# CNEPuckCPURevF.net
KiCad netlist of a schematic drawn in Altium Designer
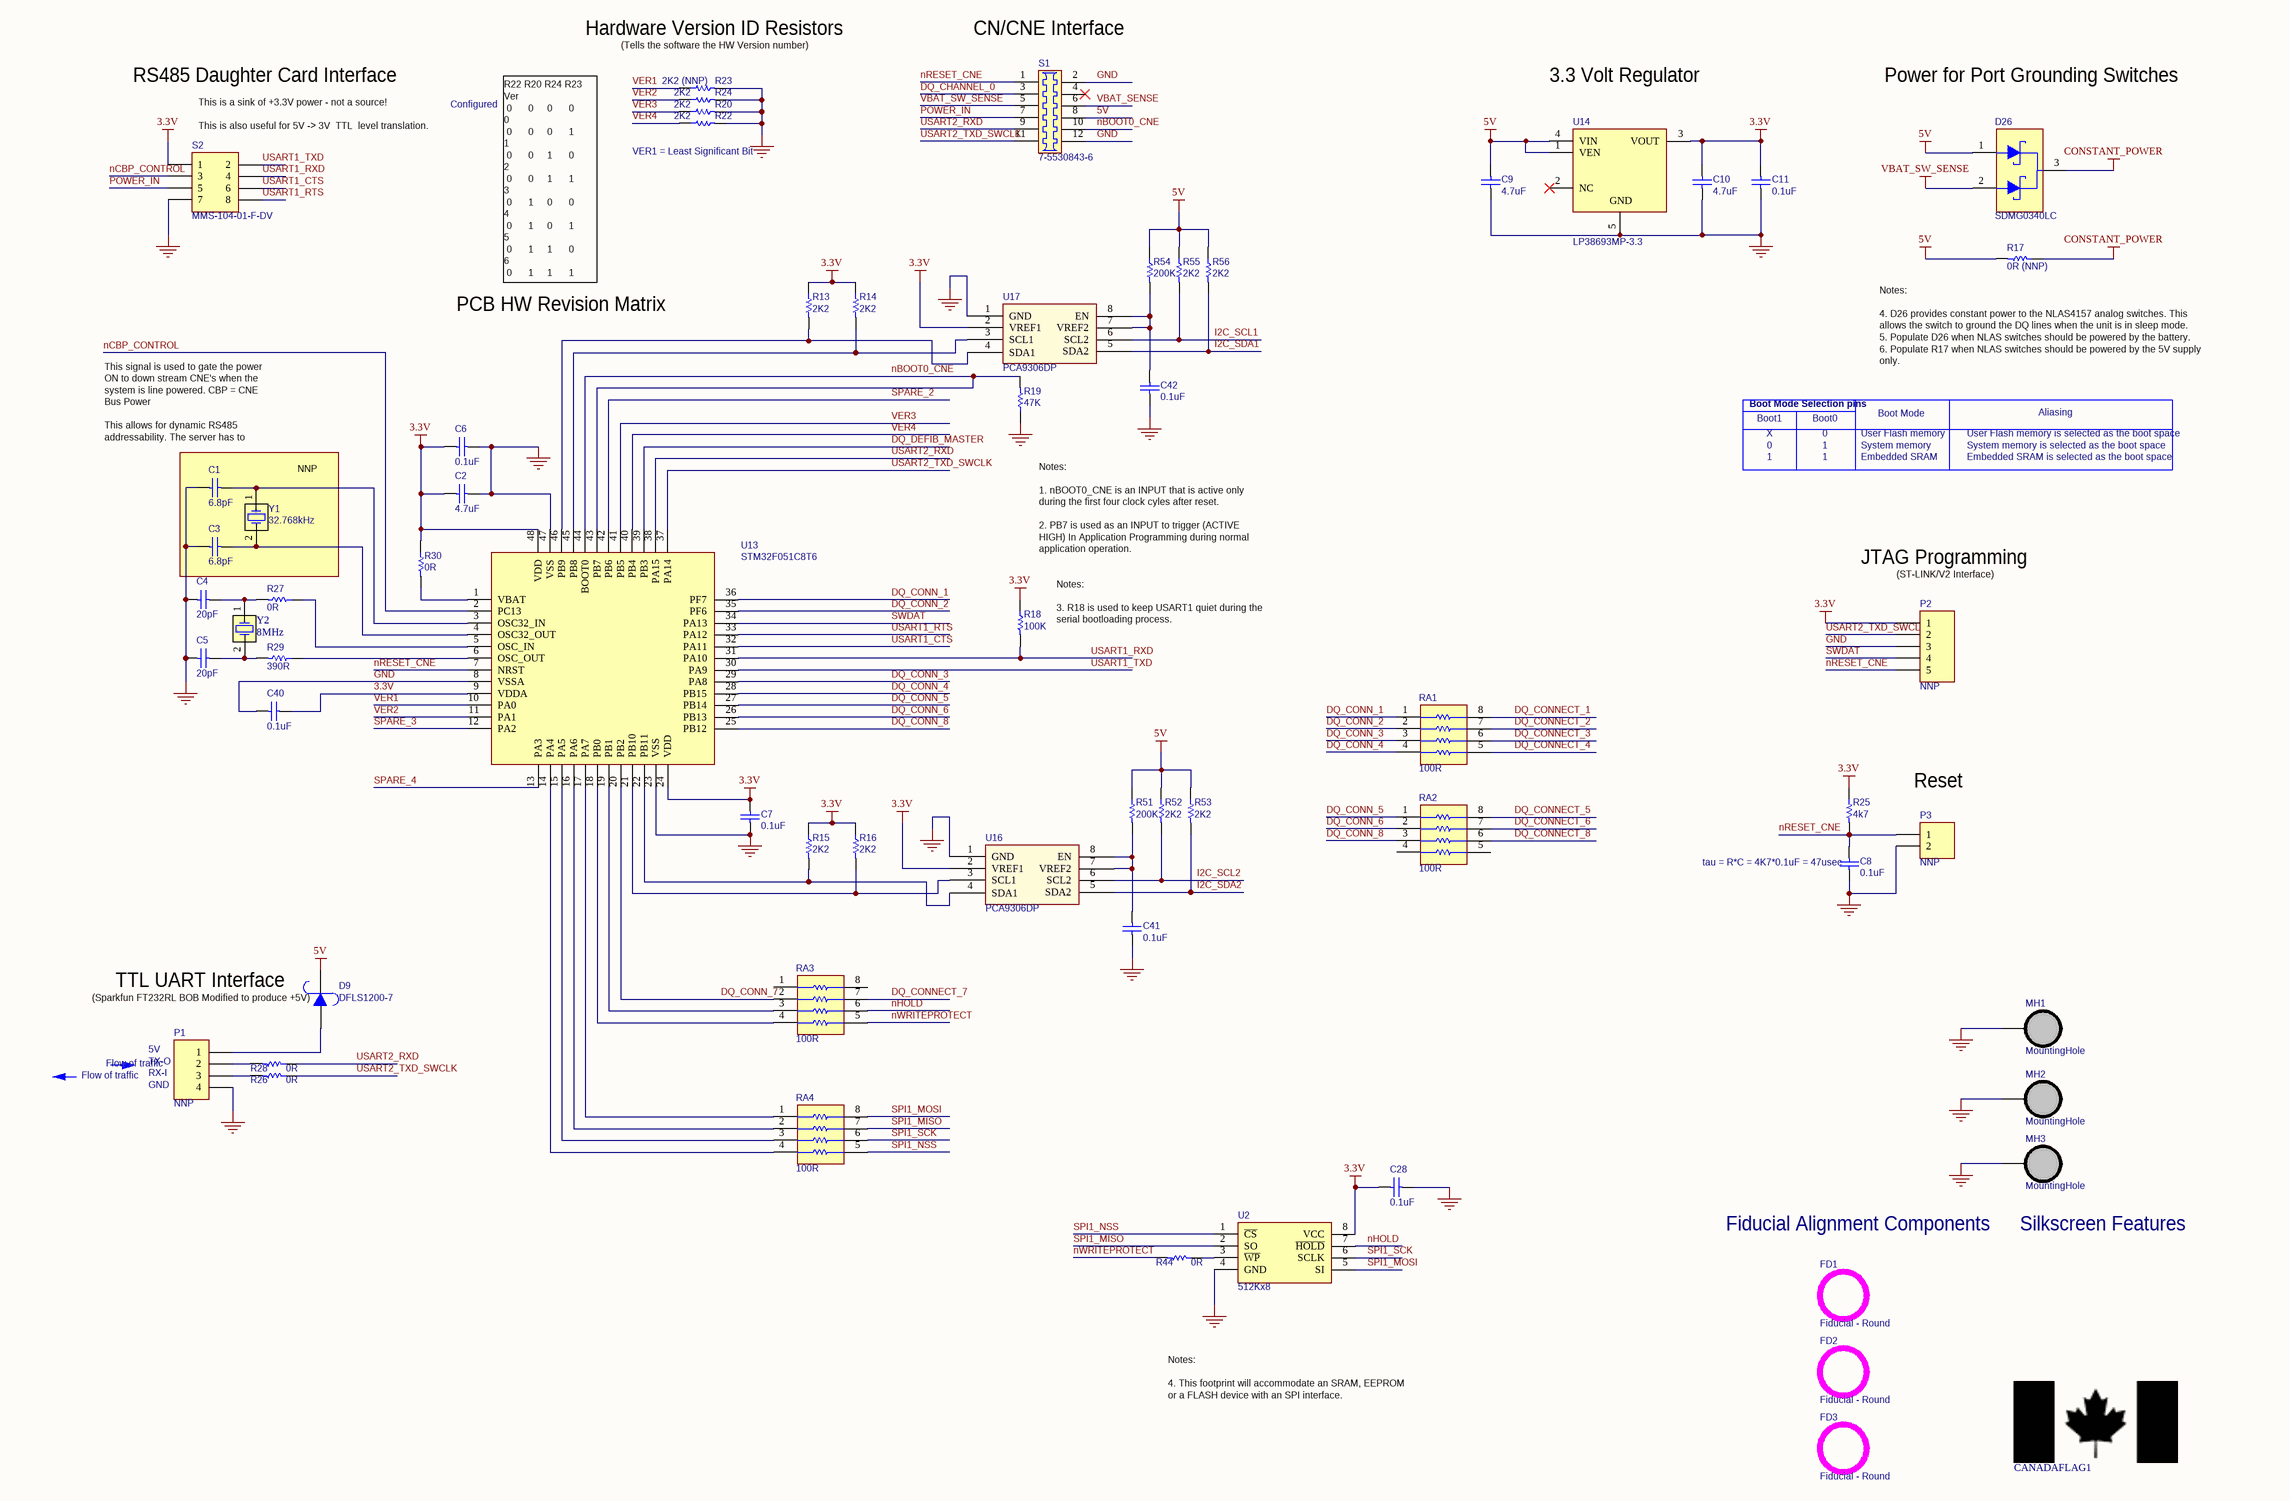
[diagram p0: CNEPuckCPURevF.SchDoc]

(export (version "E")
  (design (tool "Eeschema 10.0.6"))
  (components
    (comp (ref "C1")
      (value "6.8pF")
      (footprint "RC0603")
      (description "CAP CER 6.8PF 50V NP0 0603")
      (fields
        (field (name "MANUFACTURER") "TDK Corporation")
        (field (name "MANUFACTURER PART NUMBER") "C1608C0G1H6R8D")
      )
      (libsource (lib "Swage") (part "C1608C0G1H6R8D"))
    )
    (comp (ref "C2")
      (value "4.7uF")
      (footprint "RC0603")
      (description "CAP CER 4.7UF 10V 10% X5R 0603")
      (fields
        (field (name "MANUFACTURER") "TDK Corporation")
        (field (name "MANUFACTURER PART NUMBER") "C1608X5R1A475K/0.50")
      )
      (libsource (lib "Swage") (part "C1608X5R1A475K/0.50"))
    )
    (comp (ref "C3")
      (value "6.8pF")
      (footprint "RC0603")
      (description "CAP CER 6.8PF 50V NP0 0603")
      (fields
        (field (name "MANUFACTURER") "TDK Corporation")
        (field (name "MANUFACTURER PART NUMBER") "C1608C0G1H6R8D")
      )
      (libsource (lib "Swage") (part "C1608C0G1H6R8D"))
    )
    (comp (ref "C4")
      (value "20pF")
      (footprint "RC0603")
      (description "CAP CER 20PF 50V 5% NPO 0603")
      (fields
        (field (name "MANUFACTURER") "Yageo")
        (field (name "MANUFACTURER PART NUMBER") "CC0603JRNPO9BN200")
      )
      (libsource (lib "Swage") (part "CC0603JRNPO9BN200"))
    )
    (comp (ref "C5")
      (value "20pF")
      (footprint "RC0603")
      (description "CAP CER 20PF 50V 5% NPO 0603")
      (fields
        (field (name "MANUFACTURER") "Yageo")
        (field (name "MANUFACTURER PART NUMBER") "CC0603JRNPO9BN200")
      )
      (libsource (lib "Swage") (part "CC0603JRNPO9BN200"))
    )
    (comp (ref "C6")
      (value "0.1uF")
      (footprint "RC0603")
      (description "CAP CERM .1UF 10% 16V X7R 0603")
      (fields (field (name "TOLERANCE") "±10%") (field (name "MANUFACTURER PART NUMBER") "0603YC104KAT2A"))
      (libsource (lib "Swage") (part "0603YC104KAT2A"))
    )
    (comp (ref "C7")
      (value "0.1uF")
      (footprint "RC0603")
      (description "CAP CERM .1UF 10% 16V X7R 0603")
      (fields (field (name "TOLERANCE") "±10%") (field (name "MANUFACTURER PART NUMBER") "0603YC104KAT2A"))
      (libsource (lib "Swage") (part "0603YC104KAT2A"))
    )
    (comp (ref "C8")
      (value "0.1uF")
      (footprint "RC0603")
      (description "CAP CERM .1UF 10% 16V X7R 0603")
      (fields (field (name "TOLERANCE") "±10%") (field (name "MANUFACTURER PART NUMBER") "0603YC104KAT2A"))
      (libsource (lib "Swage") (part "0603YC104KAT2A"))
    )
    (comp (ref "C9")
      (value "4.7uF")
      (footprint "RC0603")
      (description "CAP CER 4.7UF 10V 10% X5R 0603")
      (fields
        (field (name "MANUFACTURER") "TDK Corporation")
        (field (name "MANUFACTURER PART NUMBER") "C1608X5R1A475K/0.50")
      )
      (libsource (lib "Swage") (part "C1608X5R1A475K/0.50"))
    )
    (comp (ref "C10")
      (value "4.7uF")
      (footprint "RC0603")
      (description "CAP CER 4.7UF 10V 10% X5R 0603")
      (fields
        (field (name "MANUFACTURER") "TDK Corporation")
        (field (name "MANUFACTURER PART NUMBER") "C1608X5R1A475K/0.50")
      )
      (libsource (lib "Swage") (part "C1608X5R1A475K/0.50"))
    )
    (comp (ref "C11")
      (value "0.1uF")
      (footprint "RC0603")
      (description "CAP CERM .1UF 10% 16V X7R 0603")
      (fields (field (name "TOLERANCE") "±10%") (field (name "MANUFACTURER PART NUMBER") "0603YC104KAT2A"))
      (libsource (lib "Swage") (part "0603YC104KAT2A"))
    )
    (comp (ref "C28")
      (value "0.1uF")
      (footprint "RC0603")
      (description "CAP CERM .1UF 10% 16V X7R 0603")
      (fields (field (name "TOLERANCE") "±10%") (field (name "MANUFACTURER PART NUMBER") "0603YC104KAT2A"))
      (libsource (lib "Swage") (part "0603YC104KAT2A"))
    )
    (comp (ref "C40")
      (value "0.1uF")
      (footprint "RC0603")
      (description "CAP CERM .1UF 10% 16V X7R 0603")
      (fields (field (name "TOLERANCE") "±10%") (field (name "MANUFACTURER PART NUMBER") "0603YC104KAT2A"))
      (libsource (lib "Swage") (part "0603YC104KAT2A"))
    )
    (comp (ref "C41")
      (value "0.1uF")
      (footprint "RC0603")
      (description "CAP CERM .1UF 10% 16V X7R 0603")
      (fields (field (name "TOLERANCE") "±10%") (field (name "MANUFACTURER PART NUMBER") "0603YC104KAT2A"))
      (libsource (lib "Swage") (part "0603YC104KAT2A"))
    )
    (comp (ref "C42")
      (value "0.1uF")
      (footprint "RC0603")
      (description "CAP CERM .1UF 10% 16V X7R 0603")
      (fields (field (name "TOLERANCE") "±10%") (field (name "MANUFACTURER PART NUMBER") "0603YC104KAT2A"))
      (libsource (lib "Swage") (part "0603YC104KAT2A"))
    )
    (comp (ref "CANADAFLAG1")
      (value "Canada Flag")
      (footprint "CanadaFlag500x250")
      (libsource (lib "Swage") (part "CanadaFlag"))
    )
    (comp (ref "D9")
      (value "DFLS1200-7")
      (footprint "POWERDI-123")
      (description "DIODE SCHOTTKY 1A 200V PWRDI 123")
      (fields (field (name "MANUFACTURER") "Diodes Inc"))
      (libsource (lib "Swage") (part "DFLS1200-7"))
    )
    (comp (ref "D26")
      (value "SDMG0340LC")
      (footprint "SOT-323")
      (description "DIODE SCHOTTKY 40V 30MA SOT323")
      (fields
        (field (name "MANUFACTURER") "Diodes Inc")
        (field (name "MANUFACTURER PART NUMBER") "SDMG0340LC-7-F")
      )
      (libsource (lib "Swage") (part "SDMG0340LC-7-F"))
    )
    (comp (ref "FD1")
      (value "Fiducial - Round")
      (footprint "FIDUCIAL ROUND SMALL")
      (description "Fiducial Round")
      (libsource (lib "StormaxV13") (part "Fiducial"))
    )
    (comp (ref "FD2")
      (value "Fiducial - Round")
      (footprint "FIDUCIAL ROUND SMALL")
      (description "Fiducial Round")
      (libsource (lib "StormaxV13") (part "Fiducial"))
    )
    (comp (ref "FD3")
      (value "Fiducial - Round")
      (footprint "FIDUCIAL ROUND SMALL")
      (description "Fiducial Round")
      (libsource (lib "StormaxV13") (part "Fiducial"))
    )
    (comp (ref "MH1")
      (value "MountingHole")
      (footprint "MountingHole")
      (description "PCB Mounting Hole, 0.150\" hole, 0.270\" Keepout")
      (libsource (lib "Swage") (part "MountingHole"))
    )
    (comp (ref "MH2")
      (value "MountingHole")
      (footprint "MountingHole")
      (description "PCB Mounting Hole, 0.150\" hole, 0.270\" Keepout")
      (libsource (lib "Swage") (part "MountingHole"))
    )
    (comp (ref "MH3")
      (value "MountingHole")
      (footprint "MountingHole")
      (description "PCB Mounting Hole, 0.150\" hole, 0.270\" Keepout")
      (libsource (lib "Swage") (part "MountingHole"))
    )
    (comp (ref "P1")
      (value "NNP")
      (footprint "HDR1X4")
      (description "Header, 4-Pin")
      (fields
        (field (name "MANUFACTURER") "3M")
        (field (name "MANUFACTURER PART NUMBER") "2340-6111TG")
        (field (name "PUBLISHER") "Altium Limited")
      )
      (libsource (lib "Swage") (part "Header 4"))
    )
    (comp (ref "P2")
      (value "NNP")
      (footprint "HDR1X5")
      (description "Header, 5-Pin")
      (fields
        (field (name "MANUFACTURER PART NUMBER") "2340-6111TG")
        (field (name "MANUFACTURER") "3M")
        (field (name "PUBLISHER") "Altium Limited")
      )
      (libsource (lib "Miscellaneous Connectors") (part "Header 5"))
    )
    (comp (ref "P3")
      (value "NNP")
      (footprint "HDR1X2")
      (description "Header, 2-Pin")
      (fields
        (field (name "MANUFACTURER") "3M")
        (field (name "MANUFACTURER PART NUMBER") "2340-6111TG")
        (field (name "PUBLISHER") "Altium Limited")
      )
      (libsource (lib "Miscellaneous Connectors") (part "Header 2"))
    )
    (comp (ref "R13")
      (value "2K2")
      (footprint "RC0603")
      (description "RES 2.2K OHM 1/10W 5% 0603 SMD")
      (fields
        (field (name "MANUFACTURER") "Panasonic Electronic Components")
        (field (name "MANUFACTURER PART NUMBER") "ERJ-3GEYJ222V")
      )
      (libsource (lib "Swage") (part "ERJ-3GEYJ222V"))
    )
    (comp (ref "R14")
      (value "2K2")
      (footprint "RC0603")
      (description "RES 2.2K OHM 1/10W 5% 0603 SMD")
      (fields
        (field (name "MANUFACTURER") "Panasonic Electronic Components")
        (field (name "MANUFACTURER PART NUMBER") "ERJ-3GEYJ222V")
      )
      (libsource (lib "Swage") (part "ERJ-3GEYJ222V"))
    )
    (comp (ref "R15")
      (value "2K2")
      (footprint "RC0603")
      (description "RES 2.2K OHM 1/10W 5% 0603 SMD")
      (fields
        (field (name "MANUFACTURER") "Panasonic Electronic Components")
        (field (name "MANUFACTURER PART NUMBER") "ERJ-3GEYJ222V")
      )
      (libsource (lib "Swage") (part "ERJ-3GEYJ222V"))
    )
    (comp (ref "R16")
      (value "2K2")
      (footprint "RC0603")
      (description "RES 2.2K OHM 1/10W 5% 0603 SMD")
      (fields
        (field (name "MANUFACTURER") "Panasonic Electronic Components")
        (field (name "MANUFACTURER PART NUMBER") "ERJ-3GEYJ222V")
      )
      (libsource (lib "Swage") (part "ERJ-3GEYJ222V"))
    )
    (comp (ref "R17")
      (value "0R (NNP)")
      (footprint "RC0603")
      (description "RES 0.0 OHM 1/10W 0603 SMD")
      (fields (field (name "TOLERANCE") "Jumper") (field (name "MANUFACTURER") "Panasonic - ECG"))
      (libsource (lib "Swage") (part "ERJ-3GEY0R00V"))
    )
    (comp (ref "R18")
      (value "100K")
      (footprint "RC0603")
      (description "RES 100K OHM 1/10W 5% 0603 SMD")
      (fields
        (field (name "MANUFACTURER") "Panasonic Electronic Components")
        (field (name "MANUFACTURER PART NUMBER") "ERJ-3GEYJ104V")
      )
      (libsource (lib "Swage") (part "ERJ-3GEYJ104V"))
    )
    (comp (ref "R19")
      (value "47K")
      (footprint "RC0603")
      (description "RES 47K OHM 1/10W 5% 0603 SMD")
      (fields (field (name "TOLERANCE") "±5%") (field (name "MANUFACTURER") "Panasonic - ECG"))
      (libsource (lib "Swage") (part "ERJ-3GEYJ473V"))
    )
    (comp (ref "R20")
      (value "2K2")
      (footprint "RC0603")
      (description "RES 2.2K OHM 1/10W 5% 0603 SMD")
      (fields
        (field (name "MANUFACTURER") "Panasonic Electronic Components")
        (field (name "MANUFACTURER PART NUMBER") "ERJ-3GEYJ222V")
      )
      (libsource (lib "Swage") (part "ERJ-3GEYJ222V"))
    )
    (comp (ref "R22")
      (value "2K2")
      (footprint "RC0603")
      (description "RES 2.2K OHM 1/10W 5% 0603 SMD")
      (fields
        (field (name "MANUFACTURER") "Panasonic Electronic Components")
        (field (name "MANUFACTURER PART NUMBER") "ERJ-3GEYJ222V")
      )
      (libsource (lib "Swage") (part "ERJ-3GEYJ222V"))
    )
    (comp (ref "R23")
      (value "2K2 (NNP)")
      (footprint "RC0603")
      (description "RES 2.2K OHM 1/10W 5% 0603 SMD")
      (fields
        (field (name "MANUFACTURER") "Panasonic Electronic Components")
        (field (name "MANUFACTURER PART NUMBER") "ERJ-3GEYJ222V")
      )
      (libsource (lib "Swage") (part "ERJ-3GEYJ222V"))
    )
    (comp (ref "R24")
      (value "2K2")
      (footprint "RC0603")
      (description "RES 2.2K OHM 1/10W 5% 0603 SMD")
      (fields
        (field (name "MANUFACTURER") "Panasonic Electronic Components")
        (field (name "MANUFACTURER PART NUMBER") "ERJ-3GEYJ222V")
      )
      (libsource (lib "Swage") (part "ERJ-3GEYJ222V"))
    )
    (comp (ref "R25")
      (value "4k7")
      (footprint "RC0603")
      (description "RES 4.7K OHM 1/10W 5% 0603 SMD")
      (fields
        (field (name "MANUFACTURER") "Panasonic - ECG")
        (field (name "MANUFACTURER PART NUMBER") "ERJ-3GEYJ472V")
      )
      (libsource (lib "Swage") (part "ERJ-3GEYJ472V"))
    )
    (comp (ref "R26")
      (value "0R")
      (footprint "RC0603")
      (description "RES 0.0 OHM 1/10W 0603 SMD")
      (fields (field (name "TOLERANCE") "Jumper") (field (name "MANUFACTURER") "Panasonic - ECG"))
      (libsource (lib "Swage") (part "ERJ-3GEY0R00V"))
    )
    (comp (ref "R27")
      (value "0R")
      (footprint "RC0603")
      (description "RES 0.0 OHM 1/10W 0603 SMD")
      (fields (field (name "TOLERANCE") "Jumper") (field (name "MANUFACTURER") "Panasonic - ECG"))
      (libsource (lib "Swage") (part "ERJ-3GEY0R00V"))
    )
    (comp (ref "R28")
      (value "0R")
      (footprint "RC0603")
      (description "RES 0.0 OHM 1/10W 0603 SMD")
      (fields (field (name "TOLERANCE") "Jumper") (field (name "MANUFACTURER") "Panasonic - ECG"))
      (libsource (lib "Swage") (part "ERJ-3GEY0R00V"))
    )
    (comp (ref "R29")
      (value "390R")
      (footprint "RC0603")
      (description "RES 390 OHM 1/10W 5% 0603 SMD")
      (fields
        (field (name "MANUFACTURER") "Panasonic Electronic Components")
        (field (name "MANUFACTURER PART NUMBER") "ERJ-3GEYJ391V")
      )
      (libsource (lib "Swage") (part "ERJ-3GEYJ391V"))
    )
    (comp (ref "R30")
      (value "0R")
      (footprint "RC0603")
      (description "RES 0.0 OHM 1/10W 0603 SMD")
      (fields (field (name "TOLERANCE") "Jumper") (field (name "MANUFACTURER") "Panasonic - ECG"))
      (libsource (lib "Swage") (part "ERJ-3GEY0R00V"))
    )
    (comp (ref "R44")
      (value "0R")
      (footprint "RC0603")
      (description "RES 0.0 OHM 1/10W 0603 SMD")
      (fields (field (name "TOLERANCE") "Jumper") (field (name "MANUFACTURER") "Panasonic - ECG"))
      (libsource (lib "Swage") (part "ERJ-3GEY0R00V"))
    )
    (comp (ref "R51")
      (value "200K")
      (footprint "RC0603")
      (description "RES 200K OHM 1/10W 5% 0603 SMD")
      (fields
        (field (name "MANUFACTURER") "Panasonic Electronic Components")
        (field (name "MANUFACTURER PART NUMBER") "ERJ-3GEYJ204V")
      )
      (libsource (lib "Swage") (part "ERJ-3GEYJ204V"))
    )
    (comp (ref "R52")
      (value "2K2")
      (footprint "RC0603")
      (description "RES 2.2K OHM 1/10W 5% 0603 SMD")
      (fields
        (field (name "MANUFACTURER") "Panasonic Electronic Components")
        (field (name "MANUFACTURER PART NUMBER") "ERJ-3GEYJ222V")
      )
      (libsource (lib "Swage") (part "ERJ-3GEYJ222V"))
    )
    (comp (ref "R53")
      (value "2K2")
      (footprint "RC0603")
      (description "RES 2.2K OHM 1/10W 5% 0603 SMD")
      (fields
        (field (name "MANUFACTURER") "Panasonic Electronic Components")
        (field (name "MANUFACTURER PART NUMBER") "ERJ-3GEYJ222V")
      )
      (libsource (lib "Swage") (part "ERJ-3GEYJ222V"))
    )
    (comp (ref "R54")
      (value "200K")
      (footprint "RC0603")
      (description "RES 200K OHM 1/10W 5% 0603 SMD")
      (fields
        (field (name "MANUFACTURER") "Panasonic Electronic Components")
        (field (name "MANUFACTURER PART NUMBER") "ERJ-3GEYJ204V")
      )
      (libsource (lib "Swage") (part "ERJ-3GEYJ204V"))
    )
    (comp (ref "R55")
      (value "2K2")
      (footprint "RC0603")
      (description "RES 2.2K OHM 1/10W 5% 0603 SMD")
      (fields
        (field (name "MANUFACTURER") "Panasonic Electronic Components")
        (field (name "MANUFACTURER PART NUMBER") "ERJ-3GEYJ222V")
      )
      (libsource (lib "Swage") (part "ERJ-3GEYJ222V"))
    )
    (comp (ref "R56")
      (value "2K2")
      (footprint "RC0603")
      (description "RES 2.2K OHM 1/10W 5% 0603 SMD")
      (fields
        (field (name "MANUFACTURER") "Panasonic Electronic Components")
        (field (name "MANUFACTURER PART NUMBER") "ERJ-3GEYJ222V")
      )
      (libsource (lib "Swage") (part "ERJ-3GEYJ222V"))
    )
    (comp (ref "RA1")
      (value "100R")
      (footprint "exb28v")
      (description "RES ARRAY 100 OHM 4 RES 0804")
      (fields
        (field (name "MANUFACTURER") "Panasonic Electronic Components")
        (field (name "MANUFACTURER PART NUMBER") "EXB-28V101JX")
      )
      (libsource (lib "Swage") (part "EXB-28V101JX"))
    )
    (comp (ref "RA2")
      (value "100R")
      (footprint "exb28v")
      (description "RES ARRAY 100 OHM 4 RES 0804")
      (fields
        (field (name "MANUFACTURER") "Panasonic Electronic Components")
        (field (name "MANUFACTURER PART NUMBER") "EXB-28V101JX")
      )
      (libsource (lib "Swage") (part "EXB-28V101JX"))
    )
    (comp (ref "RA3")
      (value "100R")
      (footprint "exb28v")
      (description "RES ARRAY 100 OHM 4 RES 0804")
      (fields
        (field (name "MANUFACTURER") "Panasonic Electronic Components")
        (field (name "MANUFACTURER PART NUMBER") "EXB-28V101JX")
      )
      (libsource (lib "Swage") (part "EXB-28V101JX"))
    )
    (comp (ref "RA4")
      (value "100R")
      (footprint "exb28v")
      (description "RES ARRAY 100 OHM 4 RES 0804")
      (fields
        (field (name "MANUFACTURER") "Panasonic Electronic Components")
        (field (name "MANUFACTURER PART NUMBER") "EXB-28V101JX")
      )
      (libsource (lib "Swage") (part "EXB-28V101JX"))
    )
    (comp (ref "S1")
      (value "7-5530843-6")
      (footprint "EdgeConnector-6-12")
      (description "CONN EDGECARD 6POS .100 VERT")
      (fields (field (name "MANUFACTURER") "TE Connectivity"))
      (libsource (lib "Swage") (part "7-5530843-6"))
    )
    (comp (ref "S2")
      (value "MMS-104-01-F-DV")
      (footprint "hirose-2x4")
      (description "CONN RCPT 2MM 8POS DL VERT PCB")
      (fields (field (name "MANUFACTURER") "Samtec Inc"))
      (libsource (lib "Swage") (part "MMS-104-01-F-DV"))
    )
    (comp (ref "U2")
      (value "512Kx8")
      (footprint "SOIC127P600X265-8N")
      (description "IC SRAM SPI 512K 2.5V 8SOIC")
      (fields
        (field (name "MANUFACTURER") "Microchip Technology")
        (field (name "MANUFACTURER PART NUMBER") "23LCV512-I/SN")
      )
      (libsource (lib "Swage") (part "23LCV512-I/SN"))
    )
    (comp (ref "U13")
      (value "STM32F051C8T6")
      (footprint "LQFP48-7x7mm")
      (description "IC MCU 32BIT 64KB FLASH 48LQFP")
      (fields (field (name "MANUFACTURER") "STMicroelectronics"))
      (libsource (lib "Swage") (part "STM32F051C8T6"))
    )
    (comp (ref "U14")
      (value "LP38693MP-3.3")
      (footprint "SOT223")
      (description "IC REG LDO 500MA 3.3V SOT223-4")
      (fields
        (field (name "MANUFACTURER") "National Semiconductor")
        (field (name "MANUFACTURER PART NUMBER") "LP38693MP-3.3/NOPB")
      )
      (libsource (lib "Swage") (part "LP38693MP-3.3/NOPB"))
    )
    (comp (ref "U16")
      (value "PCA9306DP")
      (footprint "TSOP65P640X120-8N")
      (description "IC LEVEL TRANSLATOR - TSSOP8")
      (fields
        (field (name "MANUFACTURER") "ON Semiconductor")
        (field (name "MANUFACTURER PART NUMBER") "PCA9306DTR2G")
      )
      (libsource (lib "Swage") (part "PCA9306DP"))
    )
    (comp (ref "U17")
      (value "PCA9306DP")
      (footprint "TSOP65P640X120-8N")
      (description "IC LEVEL TRANSLATOR - TSSOP8")
      (fields
        (field (name "MANUFACTURER") "ON Semiconductor")
        (field (name "MANUFACTURER PART NUMBER") "PCA9306DTR2G")
      )
      (libsource (lib "Swage") (part "PCA9306DP"))
    )
    (comp (ref "Y1")
      (value "32.768kHz")
      (footprint "FX135")
      (description "CRYSTAL 32.768KHZ 12.5PF SMD")
      (fields
        (field (name "MANUFACTURER") "Fox Electronics")
        (field (name "MANUFACTURER PART NUMBER") "FX135A-327")
      )
      (libsource (lib "Swage") (part "FX135A-327"))
    )
    (comp (ref "Y2")
      (value "8MHz")
      (footprint "NX8045GB")
      (description "CRYSTAL 8.000000 MHZ 8PF SMD")
      (fields
        (field (name "MANUFACTURER") "NDK")
        (field (name "MANUFACTURER PART NUMBER") "NX8045GB-8.000000MHZ")
      )
      (libsource (lib "Swage") (part "NX8045GB-8.000000MHZ"))
    )
  )
  (nets
    (net (code "1") (name "/DQ_CHANNEL_0") (class "Default")
      (node (ref "S1") (pin "3") (pinfunction "DESIGNATOR=3_3") (pintype "passive"))
    )
    (net (code "2") (name "/DQ_CONNECT_1") (class "Default")
      (node (ref "RA1") (pin "8") (pinfunction "8_8") (pintype "passive"))
    )
    (net (code "3") (name "/DQ_CONNECT_2") (class "Default")
      (node (ref "RA1") (pin "7") (pinfunction "7_7") (pintype "passive"))
    )
    (net (code "4") (name "/DQ_CONNECT_3") (class "Default")
      (node (ref "RA1") (pin "6") (pinfunction "6_6") (pintype "passive"))
    )
    (net (code "5") (name "/DQ_CONNECT_4") (class "Default")
      (node (ref "RA1") (pin "5") (pinfunction "5_5") (pintype "passive"))
    )
    (net (code "6") (name "/DQ_CONNECT_5") (class "Default")
      (node (ref "RA2") (pin "8") (pinfunction "8_8") (pintype "passive"))
    )
    (net (code "7") (name "/DQ_CONNECT_6") (class "Default")
      (node (ref "RA2") (pin "7") (pinfunction "7_7") (pintype "passive"))
    )
    (net (code "8") (name "/DQ_CONNECT_7") (class "Default")
      (node (ref "RA3") (pin "7") (pinfunction "7_7") (pintype "passive"))
    )
    (net (code "9") (name "/DQ_CONNECT_8") (class "Default")
      (node (ref "RA2") (pin "6") (pinfunction "6_6") (pintype "passive"))
    )
    (net (code "10") (name "/DQ_CONN_1") (class "Default")
      (node (ref "RA1") (pin "1") (pinfunction "1_1") (pintype "passive"))
      (node (ref "U13") (pin "36") (pinfunction "PF7_36") (pintype "passive"))
    )
    (net (code "11") (name "/DQ_CONN_2") (class "Default")
      (node (ref "RA1") (pin "2") (pinfunction "2_2") (pintype "passive"))
      (node (ref "U13") (pin "35") (pinfunction "PF6_35") (pintype "passive"))
    )
    (net (code "12") (name "/DQ_CONN_3") (class "Default")
      (node (ref "RA1") (pin "3") (pinfunction "3_3") (pintype "passive"))
      (node (ref "U13") (pin "29") (pinfunction "PA8_29") (pintype "passive"))
    )
    (net (code "13") (name "/DQ_CONN_4") (class "Default")
      (node (ref "RA1") (pin "4") (pinfunction "4_4") (pintype "passive"))
      (node (ref "U13") (pin "28") (pinfunction "PB15_28") (pintype "passive"))
    )
    (net (code "14") (name "/DQ_CONN_5") (class "Default")
      (node (ref "RA2") (pin "1") (pinfunction "1_1") (pintype "passive"))
      (node (ref "U13") (pin "27") (pinfunction "PB14_27") (pintype "passive"))
    )
    (net (code "15") (name "/DQ_CONN_6") (class "Default")
      (node (ref "RA2") (pin "2") (pinfunction "2_2") (pintype "passive"))
      (node (ref "U13") (pin "26") (pinfunction "PB13_26") (pintype "passive"))
    )
    (net (code "16") (name "/DQ_CONN_7") (class "Default")
      (node (ref "RA3") (pin "2") (pinfunction "2_2") (pintype "passive"))
      (node (ref "U13") (pin "20") (pinfunction "PB2_20") (pintype "passive"))
    )
    (net (code "17") (name "/DQ_CONN_8") (class "Default")
      (node (ref "RA2") (pin "3") (pinfunction "3_3") (pintype "passive"))
      (node (ref "U13") (pin "25") (pinfunction "PB12_25") (pintype "passive"))
    )
    (net (code "18") (name "/DQ_DEFIB_MASTER") (class "Default")
      (node (ref "U13") (pin "39") (pinfunction "PB3_39") (pintype "passive"))
    )
    (net (code "19") (name "/I2C_SCL1") (class "Default")
      (node (ref "R55") (pin "2") (pinfunction "2_2") (pintype "passive"))
      (node (ref "U17") (pin "6") (pinfunction "SCL2_6") (pintype "passive"))
    )
    (net (code "20") (name "/I2C_SCL2") (class "Default")
      (node (ref "R52") (pin "2") (pinfunction "2_2") (pintype "passive"))
      (node (ref "U16") (pin "6") (pinfunction "SCL2_6") (pintype "passive"))
    )
    (net (code "21") (name "/I2C_SDA1") (class "Default")
      (node (ref "R56") (pin "2") (pinfunction "2_2") (pintype "passive"))
      (node (ref "U17") (pin "5") (pinfunction "SDA2_5") (pintype "passive"))
    )
    (net (code "22") (name "/I2C_SDA2") (class "Default")
      (node (ref "R53") (pin "2") (pinfunction "2_2") (pintype "passive"))
      (node (ref "U16") (pin "5") (pinfunction "SDA2_5") (pintype "passive"))
    )
    (net (code "23") (name "/POWER_IN") (class "Default")
      (node (ref "S1") (pin "7") (pinfunction "DESIGNATOR=7_7") (pintype "passive"))
      (node (ref "S2") (pin "5") (pinfunction "5_5") (pintype "passive"))
    )
    (net (code "24") (name "/SPARE_2") (class "Default")
      (node (ref "U13") (pin "42") (pinfunction "PB6_42") (pintype "passive"))
    )
    (net (code "25") (name "/SPARE_3") (class "Default")
      (node (ref "U13") (pin "12") (pinfunction "PA2_12") (pintype "passive"))
    )
    (net (code "26") (name "/SPARE_4") (class "Default")
      (node (ref "U13") (pin "13") (pinfunction "PA3_13") (pintype "passive"))
    )
    (net (code "27") (name "/SPI1_MISO") (class "Default")
      (node (ref "RA4") (pin "7") (pinfunction "7_7") (pintype "passive"))
      (node (ref "U2") (pin "2") (pinfunction "SO_2") (pintype "passive"))
    )
    (net (code "28") (name "/SPI1_MOSI") (class "Default")
      (node (ref "RA4") (pin "8") (pinfunction "8_8") (pintype "passive"))
      (node (ref "U2") (pin "5") (pinfunction "SI_5") (pintype "passive"))
    )
    (net (code "29") (name "/SPI1_NSS") (class "Default")
      (node (ref "RA4") (pin "5") (pinfunction "5_5") (pintype "passive"))
      (node (ref "U2") (pin "1") (pinfunction "~{CS}_1") (pintype "passive"))
    )
    (net (code "30") (name "/SPI1_SCK") (class "Default")
      (node (ref "RA4") (pin "6") (pinfunction "6_6") (pintype "passive"))
      (node (ref "U2") (pin "6") (pinfunction "SCLK_6") (pintype "passive"))
    )
    (net (code "31") (name "/SWDAT") (class "Default")
      (node (ref "P2") (pin "4") (pinfunction "4_4") (pintype "passive"))
      (node (ref "U13") (pin "34") (pinfunction "PA13_34") (pintype "passive"))
    )
    (net (code "32") (name "/USART1_CTS") (class "Default")
      (node (ref "S2") (pin "6") (pinfunction "6_6") (pintype "passive"))
      (node (ref "U13") (pin "32") (pinfunction "PA11_32") (pintype "passive"))
    )
    (net (code "33") (name "/USART1_RTS") (class "Default")
      (node (ref "S2") (pin "8") (pinfunction "8_8") (pintype "passive"))
      (node (ref "U13") (pin "33") (pinfunction "PA12_33") (pintype "passive"))
    )
    (net (code "34") (name "/USART1_RXD") (class "Default")
      (node (ref "R18") (pin "2") (pinfunction "2_2") (pintype "passive"))
      (node (ref "S2") (pin "4") (pinfunction "4_4") (pintype "passive"))
      (node (ref "U13") (pin "31") (pinfunction "PA10_31") (pintype "passive"))
    )
    (net (code "35") (name "/USART1_TXD") (class "Default")
      (node (ref "S2") (pin "2") (pinfunction "2_2") (pintype "passive"))
      (node (ref "U13") (pin "30") (pinfunction "PA9_30") (pintype "passive"))
    )
    (net (code "36") (name "/USART2_RXD") (class "Default")
      (node (ref "R28") (pin "2") (pinfunction "2_2") (pintype "passive"))
      (node (ref "S1") (pin "9") (pinfunction "DESIGNATOR=9_9") (pintype "passive"))
      (node (ref "U13") (pin "38") (pinfunction "PA15_38") (pintype "passive"))
    )
    (net (code "37") (name "/USART2_TXD_SWCLK") (class "Default")
      (node (ref "P2") (pin "2") (pinfunction "2_2") (pintype "passive"))
      (node (ref "R26") (pin "2") (pinfunction "2_2") (pintype "passive"))
      (node (ref "S1") (pin "11") (pinfunction "DESIGNATOR=11_11") (pintype "passive"))
      (node (ref "U13") (pin "37") (pinfunction "PA14_37") (pintype "passive"))
    )
    (net (code "38") (name "/VBAT_SENSE") (class "Default")
      (node (ref "S1") (pin "6") (pinfunction "DESIGNATOR=6_6") (pintype "passive"))
    )
    (net (code "39") (name "/VER1") (class "Default")
      (node (ref "R23") (pin "1") (pinfunction "1_1") (pintype "passive"))
      (node (ref "U13") (pin "10") (pinfunction "PA0_10") (pintype "passive"))
    )
    (net (code "40") (name "/VER2") (class "Default")
      (node (ref "R24") (pin "1") (pinfunction "1_1") (pintype "passive"))
      (node (ref "U13") (pin "11") (pinfunction "PA1_11") (pintype "passive"))
    )
    (net (code "41") (name "/VER3") (class "Default")
      (node (ref "R20") (pin "1") (pinfunction "1_1") (pintype "passive"))
      (node (ref "U13") (pin "41") (pinfunction "PB5_41") (pintype "passive"))
    )
    (net (code "42") (name "/VER4") (class "Default")
      (node (ref "R22") (pin "1") (pinfunction "1_1") (pintype "passive"))
      (node (ref "U13") (pin "40") (pinfunction "PB4_40") (pintype "passive"))
    )
    (net (code "43") (name "/nBOOT0_CNE") (class "Default")
      (node (ref "R19") (pin "2") (pinfunction "2_2") (pintype "passive"))
      (node (ref "S1") (pin "10") (pinfunction "DESIGNATOR=10_10") (pintype "passive"))
      (node (ref "U13") (pin "43") (pinfunction "PB7_43") (pintype "passive"))
      (node (ref "U13") (pin "44") (pinfunction "BOOT0_44") (pintype "passive"))
    )
    (net (code "44") (name "/nCBP_CONTROL") (class "Default")
      (node (ref "S2") (pin "3") (pinfunction "3_3") (pintype "passive"))
      (node (ref "U13") (pin "2") (pinfunction "PC13_2") (pintype "passive"))
    )
    (net (code "45") (name "/nHOLD") (class "Default")
      (node (ref "RA3") (pin "6") (pinfunction "6_6") (pintype "passive"))
      (node (ref "U2") (pin "7") (pinfunction "~{HOLD}_7") (pintype "passive"))
    )
    (net (code "46") (name "/nRESET_CNE") (class "Default")
      (node (ref "C8") (pin "2") (pinfunction "2_2") (pintype "passive"))
      (node (ref "P2") (pin "5") (pinfunction "5_5") (pintype "passive"))
      (node (ref "P3") (pin "1") (pinfunction "1_1") (pintype "passive"))
      (node (ref "R25") (pin "2") (pinfunction "2_2") (pintype "passive"))
      (node (ref "S1") (pin "1") (pinfunction "DESIGNATOR=1_1") (pintype "passive"))
      (node (ref "U13") (pin "7") (pinfunction "NRST_7") (pintype "passive"))
    )
    (net (code "47") (name "/nWRITEPROTECT") (class "Default")
      (node (ref "R44") (pin "1") (pinfunction "1_1") (pintype "passive"))
      (node (ref "RA3") (pin "5") (pinfunction "5_5") (pintype "passive"))
    )
    (net (code "48") (name "3.3V") (class "Default")
      (node (ref "C10") (pin "2") (pinfunction "2_2") (pintype "passive"))
      (node (ref "C11") (pin "2") (pinfunction "2_2") (pintype "passive"))
      (node (ref "C2") (pin "2") (pinfunction "2_2") (pintype "passive"))
      (node (ref "C28") (pin "1") (pinfunction "1_1") (pintype "passive"))
      (node (ref "C40") (pin "2") (pinfunction "2_2") (pintype "passive"))
      (node (ref "C6") (pin "1") (pinfunction "1_1") (pintype "passive"))
      (node (ref "C7") (pin "1") (pinfunction "1_1") (pintype "passive"))
      (node (ref "P2") (pin "1") (pinfunction "1_1") (pintype "passive"))
      (node (ref "R13") (pin "1") (pinfunction "1_1") (pintype "passive"))
      (node (ref "R14") (pin "1") (pinfunction "1_1") (pintype "passive"))
      (node (ref "R15") (pin "1") (pinfunction "1_1") (pintype "passive"))
      (node (ref "R16") (pin "1") (pinfunction "1_1") (pintype "passive"))
      (node (ref "R18") (pin "1") (pinfunction "1_1") (pintype "passive"))
      (node (ref "R25") (pin "1") (pinfunction "1_1") (pintype "passive"))
      (node (ref "R30") (pin "2") (pinfunction "2_2") (pintype "passive"))
      (node (ref "S2") (pin "1") (pinfunction "1_1") (pintype "passive"))
      (node (ref "U13") (pin "24") (pinfunction "VDD_24") (pintype "passive"))
      (node (ref "U13") (pin "48") (pinfunction "VDD_48") (pintype "passive"))
      (node (ref "U13") (pin "9") (pinfunction "VDDA_9") (pintype "passive"))
      (node (ref "U14") (pin "3") (pinfunction "VOUT_3") (pintype "passive"))
      (node (ref "U16") (pin "2") (pinfunction "VREF1_2") (pintype "passive"))
      (node (ref "U17") (pin "2") (pinfunction "VREF1_2") (pintype "passive"))
      (node (ref "U2") (pin "8") (pinfunction "VCC_8") (pintype "passive"))
    )
    (net (code "49") (name "5V") (class "Default")
      (node (ref "C9") (pin "2") (pinfunction "2_2") (pintype "passive"))
      (node (ref "D26") (pin "1") (pinfunction "A_1") (pintype "passive"))
      (node (ref "D9") (pin "2") (pinfunction "K_2") (pintype "passive"))
      (node (ref "R17") (pin "1") (pinfunction "1_1") (pintype "passive"))
      (node (ref "R51") (pin "1") (pinfunction "1_1") (pintype "passive"))
      (node (ref "R52") (pin "1") (pinfunction "1_1") (pintype "passive"))
      (node (ref "R53") (pin "1") (pinfunction "1_1") (pintype "passive"))
      (node (ref "R54") (pin "1") (pinfunction "1_1") (pintype "passive"))
      (node (ref "R55") (pin "1") (pinfunction "1_1") (pintype "passive"))
      (node (ref "R56") (pin "1") (pinfunction "1_1") (pintype "passive"))
      (node (ref "S1") (pin "8") (pinfunction "DESIGNATOR=8_8") (pintype "passive"))
      (node (ref "U14") (pin "1") (pinfunction "VEN_1") (pintype "passive"))
      (node (ref "U14") (pin "4") (pinfunction "VIN_4") (pintype "passive"))
    )
    (net (code "50") (name "CONSTANT_POWER") (class "Default")
      (node (ref "D26") (pin "3") (pinfunction "K_3") (pintype "passive"))
      (node (ref "R17") (pin "2") (pinfunction "2_2") (pintype "passive"))
    )
    (net (code "51") (name "GND") (class "Default")
      (node (ref "C1") (pin "2") (pinfunction "2_2") (pintype "passive"))
      (node (ref "C10") (pin "1") (pinfunction "1_1") (pintype "passive"))
      (node (ref "C11") (pin "1") (pinfunction "1_1") (pintype "passive"))
      (node (ref "C2") (pin "1") (pinfunction "1_1") (pintype "passive"))
      (node (ref "C28") (pin "2") (pinfunction "2_2") (pintype "passive"))
      (node (ref "C3") (pin "2") (pinfunction "2_2") (pintype "passive"))
      (node (ref "C4") (pin "1") (pinfunction "1_1") (pintype "passive"))
      (node (ref "C40") (pin "1") (pinfunction "1_1") (pintype "passive"))
      (node (ref "C41") (pin "2") (pinfunction "2_2") (pintype "passive"))
      (node (ref "C42") (pin "2") (pinfunction "2_2") (pintype "passive"))
      (node (ref "C5") (pin "1") (pinfunction "1_1") (pintype "passive"))
      (node (ref "C6") (pin "2") (pinfunction "2_2") (pintype "passive"))
      (node (ref "C7") (pin "2") (pinfunction "2_2") (pintype "passive"))
      (node (ref "C8") (pin "1") (pinfunction "1_1") (pintype "passive"))
      (node (ref "C9") (pin "1") (pinfunction "1_1") (pintype "passive"))
      (node (ref "MH1") (pin "1") (pinfunction "1_1") (pintype "passive"))
      (node (ref "MH2") (pin "1") (pinfunction "1_1") (pintype "passive"))
      (node (ref "MH3") (pin "1") (pinfunction "1_1") (pintype "passive"))
      (node (ref "P1") (pin "4") (pinfunction "4_4") (pintype "passive"))
      (node (ref "P2") (pin "3") (pinfunction "3_3") (pintype "passive"))
      (node (ref "P3") (pin "2") (pinfunction "2_2") (pintype "passive"))
      (node (ref "R19") (pin "1") (pinfunction "1_1") (pintype "passive"))
      (node (ref "R20") (pin "2") (pinfunction "2_2") (pintype "passive"))
      (node (ref "R22") (pin "2") (pinfunction "2_2") (pintype "passive"))
      (node (ref "R23") (pin "2") (pinfunction "2_2") (pintype "passive"))
      (node (ref "R24") (pin "2") (pinfunction "2_2") (pintype "passive"))
      (node (ref "S1") (pin "12") (pinfunction "DESIGNATOR=12_12") (pintype "passive"))
      (node (ref "S1") (pin "2") (pinfunction "DESIGNATOR=2_2") (pintype "passive"))
      (node (ref "S2") (pin "7") (pinfunction "7_7") (pintype "passive"))
      (node (ref "U13") (pin "23") (pinfunction "VSS_23") (pintype "passive"))
      (node (ref "U13") (pin "47") (pinfunction "VSS_47") (pintype "passive"))
      (node (ref "U13") (pin "8") (pinfunction "VSSA_8") (pintype "passive"))
      (node (ref "U14") (pin "5") (pinfunction "GND_5") (pintype "passive"))
      (node (ref "U16") (pin "1") (pinfunction "GND_1") (pintype "passive"))
      (node (ref "U17") (pin "1") (pinfunction "GND_1") (pintype "passive"))
      (node (ref "U2") (pin "4") (pinfunction "GND_4") (pintype "passive"))
    )
    (net (code "52") (name "Net-(D9-A)") (class "Default")
      (node (ref "D9") (pin "1") (pinfunction "A_1") (pintype "passive"))
      (node (ref "P1") (pin "1") (pinfunction "1_1") (pintype "passive"))
    )
    (net (code "53") (name "Net-(P1-Pad2)") (class "Default")
      (node (ref "P1") (pin "2") (pinfunction "2_2") (pintype "passive"))
      (node (ref "R28") (pin "1") (pinfunction "1_1") (pintype "passive"))
    )
    (net (code "54") (name "Net-(P1-Pad3)") (class "Default")
      (node (ref "P1") (pin "3") (pinfunction "3_3") (pintype "passive"))
      (node (ref "R26") (pin "1") (pinfunction "1_1") (pintype "passive"))
    )
    (net (code "55") (name "Net-(U2-~{WP})") (class "Default")
      (node (ref "R44") (pin "2") (pinfunction "2_2") (pintype "passive"))
      (node (ref "U2") (pin "3") (pinfunction "~{WP}_3") (pintype "passive"))
    )
    (net (code "56") (name "Net-(U13-OSC32_IN)") (class "Default")
      (node (ref "C1") (pin "1") (pinfunction "1_1") (pintype "passive"))
      (node (ref "U13") (pin "3") (pinfunction "OSC32_IN_3") (pintype "passive"))
      (node (ref "Y1") (pin "1") (pinfunction "OSC1_1") (pintype "passive"))
    )
    (net (code "57") (name "Net-(U13-OSC32_OUT)") (class "Default")
      (node (ref "C3") (pin "1") (pinfunction "1_1") (pintype "passive"))
      (node (ref "U13") (pin "4") (pinfunction "OSC32_OUT_4") (pintype "passive"))
      (node (ref "Y1") (pin "2") (pinfunction "OSC2_2") (pintype "passive"))
    )
    (net (code "58") (name "Net-(U13-OSC_IN)") (class "Default")
      (node (ref "R27") (pin "2") (pinfunction "2_2") (pintype "passive"))
      (node (ref "U13") (pin "5") (pinfunction "OSC_IN_5") (pintype "passive"))
    )
    (net (code "59") (name "Net-(U13-OSC_OUT)") (class "Default")
      (node (ref "R29") (pin "1") (pinfunction "1_1") (pintype "passive"))
      (node (ref "U13") (pin "6") (pinfunction "OSC_OUT_6") (pintype "passive"))
    )
    (net (code "60") (name "Net-(U13-PA4)") (class "Default")
      (node (ref "RA4") (pin "4") (pinfunction "4_4") (pintype "passive"))
      (node (ref "U13") (pin "14") (pinfunction "PA4_14") (pintype "passive"))
    )
    (net (code "61") (name "Net-(U13-PA5)") (class "Default")
      (node (ref "RA4") (pin "3") (pinfunction "3_3") (pintype "passive"))
      (node (ref "U13") (pin "15") (pinfunction "PA5_15") (pintype "passive"))
    )
    (net (code "62") (name "Net-(U13-PA6)") (class "Default")
      (node (ref "RA4") (pin "2") (pinfunction "2_2") (pintype "passive"))
      (node (ref "U13") (pin "16") (pinfunction "PA6_16") (pintype "passive"))
    )
    (net (code "63") (name "Net-(U13-PA7)") (class "Default")
      (node (ref "RA4") (pin "1") (pinfunction "1_1") (pintype "passive"))
      (node (ref "U13") (pin "17") (pinfunction "PA7_17") (pintype "passive"))
    )
    (net (code "64") (name "Net-(U13-PB0)") (class "Default")
      (node (ref "RA3") (pin "4") (pinfunction "4_4") (pintype "passive"))
      (node (ref "U13") (pin "18") (pinfunction "PB0_18") (pintype "passive"))
    )
    (net (code "65") (name "Net-(U13-PB1)") (class "Default")
      (node (ref "RA3") (pin "3") (pinfunction "3_3") (pintype "passive"))
      (node (ref "U13") (pin "19") (pinfunction "PB1_19") (pintype "passive"))
    )
    (net (code "66") (name "Net-(U13-PB8)") (class "Default")
      (node (ref "R14") (pin "2") (pinfunction "2_2") (pintype "passive"))
      (node (ref "U13") (pin "45") (pinfunction "PB8_45") (pintype "passive"))
      (node (ref "U17") (pin "3") (pinfunction "SCL1_3") (pintype "passive"))
    )
    (net (code "67") (name "Net-(U13-PB9)") (class "Default")
      (node (ref "R13") (pin "2") (pinfunction "2_2") (pintype "passive"))
      (node (ref "U13") (pin "46") (pinfunction "PB9_46") (pintype "passive"))
      (node (ref "U17") (pin "4") (pinfunction "SDA1_4") (pintype "passive"))
    )
    (net (code "68") (name "Net-(U13-PB10)") (class "Default")
      (node (ref "R16") (pin "2") (pinfunction "2_2") (pintype "passive"))
      (node (ref "U13") (pin "21") (pinfunction "PB10_21") (pintype "passive"))
      (node (ref "U16") (pin "3") (pinfunction "SCL1_3") (pintype "passive"))
    )
    (net (code "69") (name "Net-(U13-PB11)") (class "Default")
      (node (ref "R15") (pin "2") (pinfunction "2_2") (pintype "passive"))
      (node (ref "U13") (pin "22") (pinfunction "PB11_22") (pintype "passive"))
      (node (ref "U16") (pin "4") (pinfunction "SDA1_4") (pintype "passive"))
    )
    (net (code "70") (name "Net-(U13-VBAT)") (class "Default")
      (node (ref "R30") (pin "1") (pinfunction "1_1") (pintype "passive"))
      (node (ref "U13") (pin "1") (pinfunction "VBAT_1") (pintype "passive"))
    )
    (net (code "71") (name "Net-(U16-EN)") (class "Default")
      (node (ref "C41") (pin "1") (pinfunction "1_1") (pintype "passive"))
      (node (ref "R51") (pin "2") (pinfunction "2_2") (pintype "passive"))
      (node (ref "U16") (pin "7") (pinfunction "VREF2_7") (pintype "passive"))
      (node (ref "U16") (pin "8") (pinfunction "EN_8") (pintype "passive"))
    )
    (net (code "72") (name "Net-(U17-EN)") (class "Default")
      (node (ref "C42") (pin "1") (pinfunction "1_1") (pintype "passive"))
      (node (ref "R54") (pin "2") (pinfunction "2_2") (pintype "passive"))
      (node (ref "U17") (pin "7") (pinfunction "VREF2_7") (pintype "passive"))
      (node (ref "U17") (pin "8") (pinfunction "EN_8") (pintype "passive"))
    )
    (net (code "73") (name "Net-(Y2-OSC1)") (class "Default")
      (node (ref "C4") (pin "2") (pinfunction "2_2") (pintype "passive"))
      (node (ref "R27") (pin "1") (pinfunction "1_1") (pintype "passive"))
      (node (ref "Y2") (pin "1") (pinfunction "OSC1_1") (pintype "passive"))
    )
    (net (code "74") (name "Net-(Y2-OSC2)") (class "Default")
      (node (ref "C5") (pin "2") (pinfunction "2_2") (pintype "passive"))
      (node (ref "R29") (pin "2") (pinfunction "2_2") (pintype "passive"))
      (node (ref "Y2") (pin "2") (pinfunction "OSC2_2") (pintype "passive"))
    )
    (net (code "75") (name "VBAT_SW_SENSE") (class "Default")
      (node (ref "D26") (pin "2") (pinfunction "A_2") (pintype "passive"))
      (node (ref "S1") (pin "5") (pinfunction "DESIGNATOR=5_5") (pintype "passive"))
    )
    (net (code "76") (name "unconnected-(RA2-Pad4)") (class "Default")
      (node (ref "RA2") (pin "4") (pinfunction "4_4") (pintype "passive"))
    )
    (net (code "77") (name "unconnected-(RA2-Pad5)") (class "Default")
      (node (ref "RA2") (pin "5") (pinfunction "5_5") (pintype "passive"))
    )
    (net (code "78") (name "unconnected-(RA3-Pad1)") (class "Default")
      (node (ref "RA3") (pin "1") (pinfunction "1_1") (pintype "passive"))
    )
    (net (code "79") (name "unconnected-(RA3-Pad8)") (class "Default")
      (node (ref "RA3") (pin "8") (pinfunction "8_8") (pintype "passive"))
    )
    (net (code "80") (name "unconnected-(S1-DESIGNATOR=4-Pad4)") (class "Default")
      (node (ref "S1") (pin "4") (pinfunction "DESIGNATOR=4_4") (pintype "passive+no_connect"))
    )
    (net (code "81") (name "unconnected-(U14-NC-Pad2)") (class "Default")
      (node (ref "U14") (pin "2") (pinfunction "NC_2") (pintype "passive+no_connect"))
    )
  )
)
